# Son_BU.net
KiCad netlist of a schematic drawn in Altium Designer
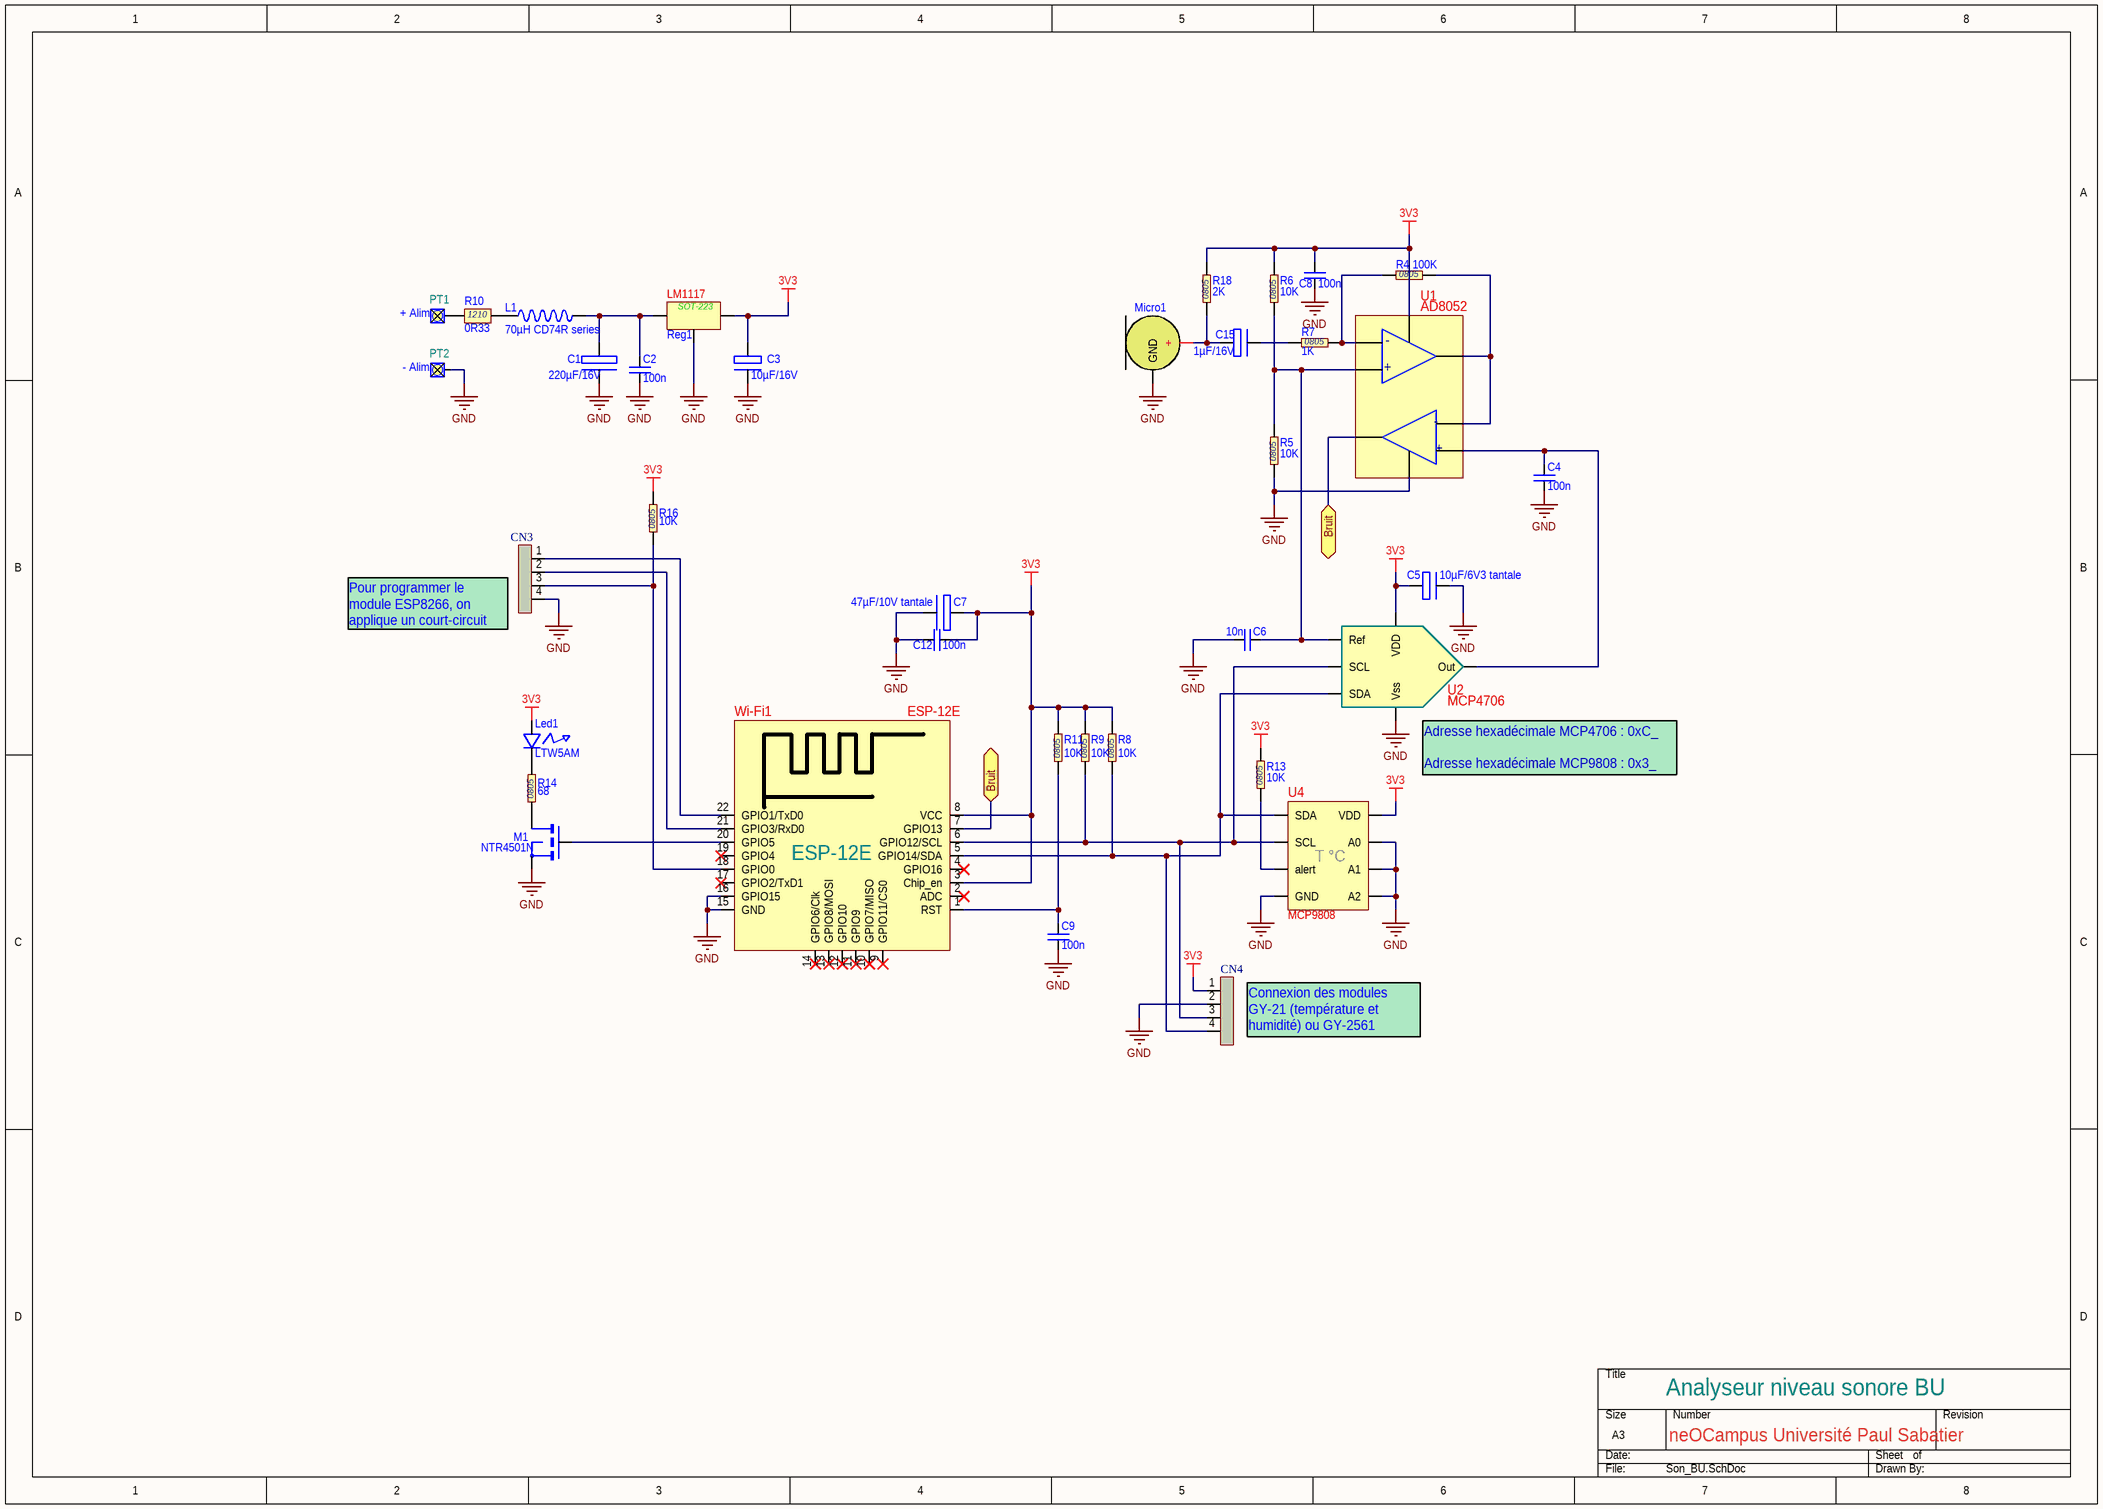
[diagram p0: Son_BU.SchDoc]

(export (version "E")
  (design (tool "Eeschema 10.0.6"))
  (components
    (comp (ref "C1")
      (value "220µF/16V")
      (footprint "7343-31")
      (description "253-5290 case 7343-31")
      (libsource (lib "CMS") (part "tantale 220µF/16V"))
    )
    (comp (ref "C2")
      (value "100n")
      (footprint "0805")
      (description "CMS 0805")
      (libsource (lib "CMS") (part "Cap_CMS_0805"))
    )
    (comp (ref "C3")
      (value "10µF/16V")
      (footprint "Tantale 10µF/16V")
      (description "145-7461 case 3216-18")
      (libsource (lib "CMS") (part "tantale 10µF/16V"))
    )
    (comp (ref "C4")
      (value "100n")
      (footprint "0805")
      (description "CMS 0805")
      (libsource (lib "CMS") (part "Cap_CMS_0805"))
    )
    (comp (ref "C5")
      (value "10µF/6V3 tantale")
      (footprint "Tantale 10µF/6V3")
      (description "175-4041 ou 145-7412 case 3216-18")
      (libsource (lib "CMS") (part "tantale 10µF/6V3"))
    )
    (comp (ref "C6")
      (value "10n")
      (footprint "0805")
      (description "CMS 0805")
      (libsource (lib "CMS") (part "Cap_CMS_0805"))
    )
    (comp (ref "C7")
      (value "47µF/10V tantale")
      (footprint "tantale 47µF/10V")
      (description "175-4168")
      (libsource (lib "CMS") (part "tantale 47µF/10V"))
    )
    (comp (ref "C8")
      (value "100n")
      (footprint "0805")
      (description "CMS 0805")
      (libsource (lib "CMS") (part "Cap_CMS_0805"))
    )
    (comp (ref "C9")
      (value "100n")
      (footprint "0805")
      (description "CMS 0805")
      (libsource (lib "CMS") (part "Cap_CMS_0805"))
    )
    (comp (ref "C12")
      (value "100n")
      (footprint "0805")
      (description "CMS 0805")
      (libsource (lib "CMS") (part "Cap_CMS_0805"))
    )
    (comp (ref "C15")
      (value "1µF/16V")
      (footprint "3216-18")
      (description "145-7406 case 3216-18")
      (libsource (lib "CMS") (part "tantale 1µF/16V"))
    )
    (comp (ref "CN3")
      (value "inch_ligne 1x4")
      (footprint "INCH_1x4_droit")
      (description "Inch_1x4_droit")
      (libsource (lib "") (part "Inch_1x4_droit_1"))
    )
    (comp (ref "CN4")
      (value "inch_ligne 1x4")
      (footprint "INCH_1x4_droit")
      (description "Inch_1x4_droit")
      (libsource (lib "Connecteurs Contacts") (part "Inch_1x4_droit"))
    )
    (comp (ref "L1")
      (value "70µH CD74R series")
      (footprint "SELF CD74R")
      (description "SMT CD74R Aliexpress")
      (libsource (lib "CMS") (part "Self CD74R"))
    )
    (comp (ref "Led1")
      (value "LTW5AM")
      (footprint "LTW5AM")
      (description "LED Golden Dragon Plus")
      (libsource (lib "CMS") (part "LTW5AM LED"))
    )
    (comp (ref "M1")
      (value "NTR4501N")
      (footprint "SOT23 (NTR4501)")
      (description "MOSFET canal N")
      (libsource (lib "Transistors Bip Mos IGBT") (part "NTR4501N"))
    )
    (comp (ref "Micro1")
      (value "Electret")
      (footprint "Micro_electret simple")
      (description "Microphone électret")
      (libsource (lib "traversants") (part "Microphone_03"))
    )
    (comp (ref "PT1")
      (value "+ Alim")
      (footprint "Pointe de test")
      (description "pointe de test CI 133-6225")
      (libsource (lib "Connecteurs Contacts") (part "PTEST"))
    )
    (comp (ref "PT2")
      (value "- Alim")
      (footprint "Pointe de test")
      (description "pointe de test CI 133-6225")
      (libsource (lib "Connecteurs Contacts") (part "PTEST"))
    )
    (comp (ref "R4")
      (value "100K")
      (footprint "0805")
      (description "CMS 0805")
      (libsource (lib "") (part "Res CMS 0805_1"))
    )
    (comp (ref "R5")
      (value "10K")
      (footprint "0805")
      (description "CMS 0805")
      (libsource (lib "CMS") (part "Res CMS 0805"))
    )
    (comp (ref "R6")
      (value "10K")
      (footprint "0805")
      (description "CMS 0805")
      (libsource (lib "CMS") (part "Res CMS 0805"))
    )
    (comp (ref "R7")
      (value "1K")
      (footprint "0805")
      (description "CMS 0805")
      (libsource (lib "") (part "Res CMS 0805_1"))
    )
    (comp (ref "R8")
      (value "10K")
      (footprint "0805")
      (description "CMS 0805")
      (libsource (lib "CMS") (part "Res CMS 0805"))
    )
    (comp (ref "R9")
      (value "10K")
      (footprint "0805")
      (description "CMS 0805")
      (libsource (lib "CMS") (part "Res CMS 0805"))
    )
    (comp (ref "R10")
      (value "0R33")
      (footprint "1210")
      (description "CMS 1210")
      (libsource (lib "CMS") (part "Res CMS 1210 ERJ14B"))
    )
    (comp (ref "R11")
      (value "10K")
      (footprint "0805")
      (description "CMS 0805")
      (libsource (lib "CMS") (part "Res CMS 0805"))
    )
    (comp (ref "R13")
      (value "10K")
      (footprint "0805")
      (description "CMS 0805")
      (libsource (lib "CMS") (part "Res CMS 0805"))
    )
    (comp (ref "R14")
      (value "68")
      (footprint "0805")
      (description "CMS 0805")
      (libsource (lib "CMS") (part "Res CMS 0805"))
    )
    (comp (ref "R16")
      (value "10K")
      (footprint "0805")
      (description "CMS 0805")
      (libsource (lib "CMS") (part "Res CMS 0805"))
    )
    (comp (ref "R18")
      (value "2K")
      (footprint "0805")
      (description "CMS 0805")
      (libsource (lib "CMS") (part "Res CMS 0805"))
    )
    (comp (ref "Reg1")
      (value "LM1117")
      (footprint "SOT223")
      (description "Régulateur SOT-223")
      (libsource (lib "Convertisseurs_Régulateurs") (part "LM1117/800mA"))
    )
    (comp (ref "U1")
      (value "AD8052")
      (footprint "SOIC08")
      (description "AOP")
      (libsource (lib "CMS") (part "AD8052"))
    )
    (comp (ref "U2")
      (value "MCP4706")
      (footprint "SOT23-6")
      (description "DAC I2C (RS : 738-7111)")
      (libsource (lib "CMS") (part "MCP4706_1"))
    )
    (comp (ref "U4")
      (value "MCP9808")
      (footprint "MSOP-08")
      (description "Digital temperature Sensor")
      (libsource (lib "CMS") (part "MCP9808"))
    )
    (comp (ref "Wi-Fi1")
      (value "ESP-12E")
      (footprint "ESP-12E")
      (description "ESP-12E module Wi-Fi")
      (libsource (lib "CMS") (part "ESP-12E"))
    )
  )
  (nets
    (net (code "1") (name "/Bruit") (class "Default")
      (node (ref "U1") (pin "7") (pinfunction "out_7") (pintype "passive"))
      (node (ref "Wi-Fi1") (pin "7") (pinfunction "GPIO13_7") (pintype "passive"))
    )
    (net (code "2") (name "3V3") (class "Default")
      (node (ref "C12") (pin "2") (pinfunction "CT2_2") (pintype "passive"))
      (node (ref "C3") (pin "1") (pinfunction "V+_1") (pintype "passive"))
      (node (ref "C5") (pin "1") (pinfunction "V+_1") (pintype "passive"))
      (node (ref "C7") (pin "1") (pinfunction "V+_1") (pintype "passive"))
      (node (ref "C8") (pin "2") (pinfunction "CT2_2") (pintype "passive"))
      (node (ref "CN4") (pin "1") (pintype "passive"))
      (node (ref "Led1") (pin "1") (pinfunction "anode_1") (pintype "passive"))
      (node (ref "R11") (pin "2") (pinfunction "CT2_2") (pintype "passive"))
      (node (ref "R13") (pin "2") (pinfunction "CT2_2") (pintype "passive"))
      (node (ref "R16") (pin "2") (pinfunction "CT2_2") (pintype "passive"))
      (node (ref "R18") (pin "2") (pinfunction "CT2_2") (pintype "passive"))
      (node (ref "R6") (pin "2") (pinfunction "CT2_2") (pintype "passive"))
      (node (ref "R8") (pin "2") (pinfunction "CT2_2") (pintype "passive"))
      (node (ref "R9") (pin "2") (pinfunction "CT2_2") (pintype "passive"))
      (node (ref "Reg1") (pin "2") (pinfunction "OUT_2") (pintype "passive"))
      (node (ref "U1") (pin "8") (pinfunction "V+_8") (pintype "passive"))
      (node (ref "U2") (pin "3") (pinfunction "VDD_3") (pintype "passive"))
      (node (ref "U4") (pin "8") (pinfunction "VDD_8") (pintype "passive"))
      (node (ref "Wi-Fi1") (pin "3") (pinfunction "Chip_en_3") (pintype "passive"))
      (node (ref "Wi-Fi1") (pin "8") (pinfunction "VCC_8") (pintype "passive"))
    )
    (net (code "3") (name "GND") (class "Default")
      (node (ref "C1") (pin "2") (pinfunction "V-_2") (pintype "passive"))
      (node (ref "C12") (pin "1") (pinfunction "CT1_1") (pintype "passive"))
      (node (ref "C2") (pin "1") (pinfunction "CT1_1") (pintype "passive"))
      (node (ref "C3") (pin "2") (pinfunction "V-_2") (pintype "passive"))
      (node (ref "C4") (pin "1") (pinfunction "CT1_1") (pintype "passive"))
      (node (ref "C5") (pin "2") (pinfunction "V-_2") (pintype "passive"))
      (node (ref "C6") (pin "2") (pinfunction "CT2_2") (pintype "passive"))
      (node (ref "C7") (pin "2") (pinfunction "V-_2") (pintype "passive"))
      (node (ref "C8") (pin "1") (pinfunction "CT1_1") (pintype "passive"))
      (node (ref "C9") (pin "1") (pinfunction "CT1_1") (pintype "passive"))
      (node (ref "CN3") (pin "4") (pintype "passive"))
      (node (ref "CN4") (pin "2") (pintype "passive"))
      (node (ref "M1") (pin "3") (pinfunction "S_3") (pintype "passive"))
      (node (ref "Micro1") (pin "0") (pinfunction "GND_0") (pintype "passive"))
      (node (ref "PT2") (pin "1") (pinfunction "PIN_1") (pintype "passive"))
      (node (ref "R5") (pin "1") (pinfunction "CT1_1") (pintype "passive"))
      (node (ref "Reg1") (pin "1") (pinfunction "GND_1") (pintype "passive"))
      (node (ref "U1") (pin "4") (pinfunction "V-_4") (pintype "passive"))
      (node (ref "U2") (pin "2") (pinfunction "Vss_2") (pintype "passive"))
      (node (ref "U4") (pin "4") (pinfunction "GND_4") (pintype "passive"))
      (node (ref "U4") (pin "5") (pinfunction "A2_5") (pintype "passive"))
      (node (ref "U4") (pin "6") (pinfunction "A1_6") (pintype "passive"))
      (node (ref "U4") (pin "7") (pinfunction "A0_7") (pintype "passive"))
      (node (ref "Wi-Fi1") (pin "15") (pinfunction "GND_15") (pintype "passive"))
      (node (ref "Wi-Fi1") (pin "16") (pinfunction "GPIO15_16") (pintype "passive"))
    )
    (net (code "4") (name "Net-(C1-V+)") (class "Default")
      (node (ref "C1") (pin "1") (pinfunction "V+_1") (pintype "passive"))
      (node (ref "C2") (pin "2") (pinfunction "CT2_2") (pintype "passive"))
      (node (ref "L1") (pin "1") (pinfunction "CT1_1") (pintype "passive"))
      (node (ref "Reg1") (pin "3") (pinfunction "IN_3") (pintype "passive"))
    )
    (net (code "5") (name "Net-(C4-CT2)") (class "Default")
      (node (ref "C4") (pin "2") (pinfunction "CT2_2") (pintype "passive"))
      (node (ref "U1") (pin "5") (pinfunction "in+_5") (pintype "passive"))
      (node (ref "U2") (pin "1") (pinfunction "Out_1") (pintype "passive"))
    )
    (net (code "6") (name "Net-(C6-CT1)") (class "Default")
      (node (ref "C6") (pin "1") (pinfunction "CT1_1") (pintype "passive"))
      (node (ref "R5") (pin "2") (pinfunction "CT2_2") (pintype "passive"))
      (node (ref "R6") (pin "1") (pinfunction "CT1_1") (pintype "passive"))
      (node (ref "U1") (pin "3") (pinfunction "in+_3") (pintype "passive"))
      (node (ref "U2") (pin "6") (pinfunction "Ref_6") (pintype "passive"))
    )
    (net (code "7") (name "Net-(C9-CT2)") (class "Default")
      (node (ref "C9") (pin "2") (pinfunction "CT2_2") (pintype "passive"))
      (node (ref "R11") (pin "1") (pinfunction "CT1_1") (pintype "passive"))
      (node (ref "Wi-Fi1") (pin "1") (pinfunction "RST_1") (pintype "passive"))
    )
    (net (code "8") (name "Net-(C15-V+)") (class "Default")
      (node (ref "C15") (pin "1") (pinfunction "V+_1") (pintype "passive"))
      (node (ref "Micro1") (pin "1") (pinfunction "+_1") (pintype "passive"))
      (node (ref "R18") (pin "1") (pinfunction "CT1_1") (pintype "passive"))
    )
    (net (code "9") (name "Net-(C15-V-)") (class "Default")
      (node (ref "C15") (pin "2") (pinfunction "V-_2") (pintype "passive"))
      (node (ref "R7") (pin "1") (pinfunction "CT1_1") (pintype "passive"))
    )
    (net (code "10") (name "Net-(L1-CT2)") (class "Default")
      (node (ref "L1") (pin "2") (pinfunction "CT2_2") (pintype "passive"))
      (node (ref "R10") (pin "2") (pinfunction "CT2_2") (pintype "passive"))
    )
    (net (code "11") (name "Net-(Led1-cathode)") (class "Default")
      (node (ref "Led1") (pin "2") (pinfunction "cathode_2") (pintype "passive"))
      (node (ref "R14") (pin "2") (pinfunction "CT2_2") (pintype "passive"))
    )
    (net (code "12") (name "Net-(M1-D)") (class "Default")
      (node (ref "M1") (pin "1") (pinfunction "D_1") (pintype "passive"))
      (node (ref "R14") (pin "1") (pinfunction "CT1_1") (pintype "passive"))
    )
    (net (code "13") (name "Net-(M1-G)") (class "Default")
      (node (ref "M1") (pin "2") (pinfunction "G_2") (pintype "passive"))
      (node (ref "Wi-Fi1") (pin "20") (pinfunction "GPIO5_20") (pintype "passive"))
    )
    (net (code "14") (name "Net-(PT1-PIN)") (class "Default")
      (node (ref "PT1") (pin "1") (pinfunction "PIN_1") (pintype "passive"))
      (node (ref "R10") (pin "1") (pinfunction "CT1_1") (pintype "passive"))
    )
    (net (code "15") (name "Net-(R4-CT1)") (class "Default")
      (node (ref "R4") (pin "1") (pinfunction "CT1_1") (pintype "passive"))
      (node (ref "R7") (pin "2") (pinfunction "CT2_2") (pintype "passive"))
      (node (ref "U1") (pin "2") (pinfunction "in-_2") (pintype "passive"))
    )
    (net (code "16") (name "Net-(R4-CT2)") (class "Default")
      (node (ref "R4") (pin "2") (pinfunction "CT2_2") (pintype "passive"))
      (node (ref "U1") (pin "1") (pinfunction "out_1") (pintype "passive"))
      (node (ref "U1") (pin "6") (pinfunction "in-_6") (pintype "passive"))
    )
    (net (code "17") (name "Net-(R8-CT1)") (class "Default")
      (node (ref "CN4") (pin "4") (pintype "passive"))
      (node (ref "R8") (pin "1") (pinfunction "CT1_1") (pintype "passive"))
      (node (ref "U2") (pin "4") (pinfunction "SDA_4") (pintype "passive"))
      (node (ref "U4") (pin "1") (pinfunction "SDA_1") (pintype "passive"))
      (node (ref "Wi-Fi1") (pin "5") (pinfunction "GPIO14/SDA_5") (pintype "passive"))
    )
    (net (code "18") (name "Net-(R9-CT1)") (class "Default")
      (node (ref "CN4") (pin "3") (pintype "passive"))
      (node (ref "R9") (pin "1") (pinfunction "CT1_1") (pintype "passive"))
      (node (ref "U2") (pin "5") (pinfunction "SCL_5") (pintype "passive"))
      (node (ref "U4") (pin "2") (pinfunction "SCL_2") (pintype "passive"))
      (node (ref "Wi-Fi1") (pin "6") (pinfunction "GPIO12/SCL_6") (pintype "passive"))
    )
    (net (code "19") (name "Net-(R13-CT1)") (class "Default")
      (node (ref "R13") (pin "1") (pinfunction "CT1_1") (pintype "passive"))
      (node (ref "U4") (pin "3") (pinfunction "alert_3") (pintype "passive"))
    )
    (net (code "20") (name "Net-(R16-CT1)") (class "Default")
      (node (ref "CN3") (pin "3") (pintype "passive"))
      (node (ref "R16") (pin "1") (pinfunction "CT1_1") (pintype "passive"))
      (node (ref "Wi-Fi1") (pin "18") (pinfunction "GPIO0_18") (pintype "passive"))
    )
    (net (code "21") (name "Net-(Wi-Fi1-GPIO1{slash}TxD0)") (class "Default")
      (node (ref "CN3") (pin "1") (pintype "passive"))
      (node (ref "Wi-Fi1") (pin "22") (pinfunction "GPIO1/TxD0_22") (pintype "passive"))
    )
    (net (code "22") (name "Net-(Wi-Fi1-GPIO3{slash}RxD0)") (class "Default")
      (node (ref "CN3") (pin "2") (pintype "passive"))
      (node (ref "Wi-Fi1") (pin "21") (pinfunction "GPIO3/RxD0_21") (pintype "passive"))
    )
    (net (code "23") (name "unconnected-(Wi-Fi1-ADC-Pad2)") (class "Default")
      (node (ref "Wi-Fi1") (pin "2") (pinfunction "ADC_2") (pintype "passive+no_connect"))
    )
    (net (code "24") (name "unconnected-(Wi-Fi1-GPIO2{slash}TxD1-Pad17)") (class "Default")
      (node (ref "Wi-Fi1") (pin "17") (pinfunction "GPIO2/TxD1_17") (pintype "passive+no_connect"))
    )
    (net (code "25") (name "unconnected-(Wi-Fi1-GPIO4-Pad19)") (class "Default")
      (node (ref "Wi-Fi1") (pin "19") (pinfunction "GPIO4_19") (pintype "passive+no_connect"))
    )
    (net (code "26") (name "unconnected-(Wi-Fi1-GPIO6{slash}Clk-Pad14)") (class "Default")
      (node (ref "Wi-Fi1") (pin "14") (pinfunction "GPIO6/Clk_14") (pintype "passive+no_connect"))
    )
    (net (code "27") (name "unconnected-(Wi-Fi1-GPIO7{slash}MISO-Pad10)") (class "Default")
      (node (ref "Wi-Fi1") (pin "10") (pinfunction "GPIO7/MISO_10") (pintype "passive+no_connect"))
    )
    (net (code "28") (name "unconnected-(Wi-Fi1-GPIO8{slash}MOSI-Pad13)") (class "Default")
      (node (ref "Wi-Fi1") (pin "13") (pinfunction "GPIO8/MOSI_13") (pintype "passive+no_connect"))
    )
    (net (code "29") (name "unconnected-(Wi-Fi1-GPIO9-Pad11)") (class "Default")
      (node (ref "Wi-Fi1") (pin "11") (pinfunction "GPIO9_11") (pintype "passive+no_connect"))
    )
    (net (code "30") (name "unconnected-(Wi-Fi1-GPIO10-Pad12)") (class "Default")
      (node (ref "Wi-Fi1") (pin "12") (pinfunction "GPIO10_12") (pintype "passive+no_connect"))
    )
    (net (code "31") (name "unconnected-(Wi-Fi1-GPIO11{slash}CS0-Pad9)") (class "Default")
      (node (ref "Wi-Fi1") (pin "9") (pinfunction "GPIO11/CS0_9") (pintype "passive+no_connect"))
    )
    (net (code "32") (name "unconnected-(Wi-Fi1-GPIO16-Pad4)") (class "Default")
      (node (ref "Wi-Fi1") (pin "4") (pinfunction "GPIO16_4") (pintype "passive+no_connect"))
    )
  )
)
